# Top_board.net
KiCad netlist of a schematic drawn in Altium Designer
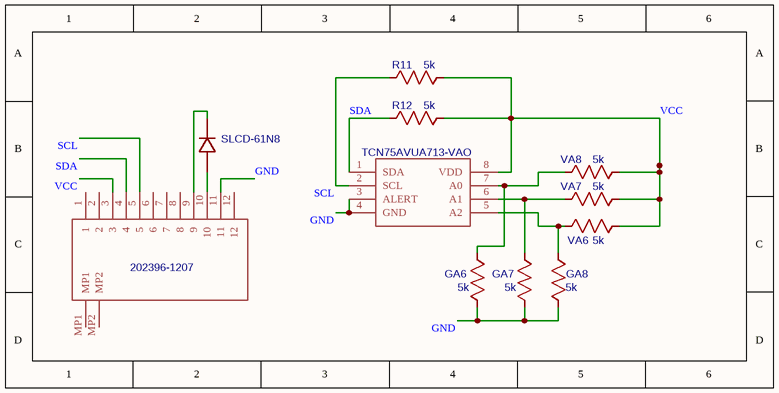
[diagram p0: Top_board.schdoc]

(export (version "E")
  (design (tool "Eeschema 10.0.6"))
  (components
    (comp (ref "D8")
      (value "SLCD-61N8")
      (footprint "SOD-123_L2.8-W1.8-LS3.7-RD")
      (fields
        (field (name "BOM_SUPPLIER PART") "C328592")
        (field (name "BOM_MANUFACTURER PART") "1N4007W")
        (field (name "CONTRIBUTOR") "Blothr")
      )
      (libsource (lib "altium-import") (part "root_1_SLCD-61N8_"))
    )
    (comp (ref "GA6")
      (value "5k")
      (footprint "R0805")
      (fields
        (field (name "BOM_SUPPLIER PART") "71-CRCW0805J-5K")
        (field (name "BOM_MANUFACTURER PART") "CRCW08055K00JNTA")
        (field (name "CONTRIBUTOR") "LCEDA_Lib")
      )
      (libsource (lib "altium-import") (part "root_1_5k_"))
    )
    (comp (ref "GA7")
      (value "5k")
      (footprint "R0805")
      (fields
        (field (name "BOM_SUPPLIER PART") "71-CRCW0805J-5K")
        (field (name "BOM_MANUFACTURER PART") "CRCW08055K00JNTA")
        (field (name "CONTRIBUTOR") "LCEDA_Lib")
      )
      (libsource (lib "altium-import") (part "root_1_5k_"))
    )
    (comp (ref "GA8")
      (value "5k")
      (footprint "R0805")
      (fields
        (field (name "BOM_SUPPLIER PART") "71-CRCW0805J-5K")
        (field (name "BOM_MANUFACTURER PART") "CRCW08055K00JNTA")
        (field (name "CONTRIBUTOR") "LCEDA_Lib")
      )
      (libsource (lib "altium-import") (part "root_1_5k_"))
    )
    (comp (ref "IC3")
      (value "TCN75AVUA713-VAO")
      (footprint "SOP65P490X110-8N")
      (libsource (lib "altium-import") (part "root_0_TCN75AVUA713-VAO_"))
    )
    (comp (ref "J2")
      (value "202396-1207")
      (footprint "2023961207")
      (fields (field (name "CONTRIBUTOR") "tomact"))
      (libsource (lib "altium-import") (part "root_1_202396-1207_"))
    )
    (comp (ref "R11")
      (value "5k")
      (footprint "R0805")
      (fields
        (field (name "BOM_SUPPLIER PART") "71-CRCW0805J-5K")
        (field (name "BOM_MANUFACTURER PART") "CRCW08055K00JNTA")
        (field (name "CONTRIBUTOR") "LCEDA_Lib")
      )
      (libsource (lib "altium-import") (part "root_0_5k_"))
    )
    (comp (ref "R12")
      (value "5k")
      (footprint "R0805")
      (fields
        (field (name "BOM_SUPPLIER PART") "71-CRCW0805J-5K")
        (field (name "BOM_MANUFACTURER PART") "CRCW08055K00JNTA")
        (field (name "CONTRIBUTOR") "LCEDA_Lib")
      )
      (libsource (lib "altium-import") (part "root_0_5k_"))
    )
    (comp (ref "VA6")
      (value "5k")
      (footprint "R0805")
      (fields
        (field (name "BOM_SUPPLIER PART") "71-CRCW0805J-5K")
        (field (name "BOM_MANUFACTURER PART") "CRCW08055K00JNTA")
        (field (name "CONTRIBUTOR") "LCEDA_Lib")
      )
      (libsource (lib "altium-import") (part "root_0_5k_"))
    )
    (comp (ref "VA7")
      (value "5k")
      (footprint "R0805")
      (fields
        (field (name "BOM_SUPPLIER PART") "71-CRCW0805J-5K")
        (field (name "BOM_MANUFACTURER PART") "CRCW08055K00JNTA")
        (field (name "CONTRIBUTOR") "LCEDA_Lib")
      )
      (libsource (lib "altium-import") (part "root_0_5k_"))
    )
    (comp (ref "VA8")
      (value "5k")
      (footprint "R0805")
      (fields
        (field (name "BOM_SUPPLIER PART") "71-CRCW0805J-5K")
        (field (name "BOM_MANUFACTURER PART") "CRCW08055K00JNTA")
        (field (name "CONTRIBUTOR") "LCEDA_Lib")
      )
      (libsource (lib "altium-import") (part "root_0_5k_"))
    )
  )
  (nets
    (net (code "1") (name "/GND") (class "Default")
      (node (ref "GA6") (pin "1") (pinfunction "1_1") (pintype "passive"))
      (node (ref "GA7") (pin "1") (pinfunction "1_1") (pintype "passive"))
      (node (ref "GA8") (pin "1") (pinfunction "1_1") (pintype "passive"))
      (node (ref "IC3") (pin "3") (pinfunction "ALERT_3") (pintype "passive"))
      (node (ref "IC3") (pin "4") (pinfunction "GND_4") (pintype "passive"))
      (node (ref "J2") (pin "11") (pinfunction "11_11") (pintype "passive"))
    )
    (net (code "2") (name "/SCL") (class "Default")
      (node (ref "IC3") (pin "2") (pinfunction "SCL_2") (pintype "passive"))
      (node (ref "J2") (pin "5") (pinfunction "5_5") (pintype "passive"))
      (node (ref "R11") (pin "1") (pinfunction "1_1") (pintype "passive"))
    )
    (net (code "3") (name "/SDA") (class "Default")
      (node (ref "IC3") (pin "1") (pinfunction "SDA_1") (pintype "passive"))
      (node (ref "J2") (pin "4") (pinfunction "4_4") (pintype "passive"))
      (node (ref "R12") (pin "1") (pinfunction "1_1") (pintype "passive"))
    )
    (net (code "4") (name "/VCC") (class "Default")
      (node (ref "IC3") (pin "8") (pinfunction "VDD_8") (pintype "passive"))
      (node (ref "J2") (pin "3") (pinfunction "3_3") (pintype "passive"))
      (node (ref "R11") (pin "2") (pinfunction "2_2") (pintype "passive"))
      (node (ref "R12") (pin "2") (pinfunction "2_2") (pintype "passive"))
      (node (ref "VA6") (pin "2") (pinfunction "2_2") (pintype "passive"))
      (node (ref "VA7") (pin "2") (pinfunction "2_2") (pintype "passive"))
      (node (ref "VA8") (pin "2") (pinfunction "2_2") (pintype "passive"))
    )
    (net (code "5") (name "Net-(D8-Pad1)") (class "Default")
      (node (ref "D8") (pin "1") (pinfunction "1_1") (pintype "passive"))
      (node (ref "J2") (pin "9") (pinfunction "9_9") (pintype "passive"))
    )
    (net (code "6") (name "Net-(D8-Pad2)") (class "Default")
      (node (ref "D8") (pin "2") (pinfunction "2_2") (pintype "passive"))
      (node (ref "J2") (pin "10") (pinfunction "10_10") (pintype "passive"))
    )
    (net (code "7") (name "Net-(IC3-A0)") (class "Default")
      (node (ref "GA6") (pin "2") (pinfunction "2_2") (pintype "passive"))
      (node (ref "IC3") (pin "7") (pinfunction "A0_7") (pintype "passive"))
      (node (ref "VA8") (pin "1") (pinfunction "1_1") (pintype "passive"))
    )
    (net (code "8") (name "Net-(IC3-A1)") (class "Default")
      (node (ref "GA7") (pin "2") (pinfunction "2_2") (pintype "passive"))
      (node (ref "IC3") (pin "6") (pinfunction "A1_6") (pintype "passive"))
      (node (ref "VA7") (pin "1") (pinfunction "1_1") (pintype "passive"))
    )
    (net (code "9") (name "Net-(IC3-A2)") (class "Default")
      (node (ref "GA8") (pin "2") (pinfunction "2_2") (pintype "passive"))
      (node (ref "IC3") (pin "5") (pinfunction "A2_5") (pintype "passive"))
      (node (ref "VA6") (pin "1") (pinfunction "1_1") (pintype "passive"))
    )
    (net (code "10") (name "unconnected-(J2-Pad1)") (class "Default")
      (node (ref "J2") (pin "1") (pinfunction "1_1") (pintype "passive"))
    )
    (net (code "11") (name "unconnected-(J2-Pad2)") (class "Default")
      (node (ref "J2") (pin "2") (pinfunction "2_2") (pintype "passive"))
    )
    (net (code "12") (name "unconnected-(J2-Pad6)") (class "Default")
      (node (ref "J2") (pin "6") (pinfunction "6_6") (pintype "passive"))
    )
    (net (code "13") (name "unconnected-(J2-Pad7)") (class "Default")
      (node (ref "J2") (pin "7") (pinfunction "7_7") (pintype "passive"))
    )
    (net (code "14") (name "unconnected-(J2-Pad8)") (class "Default")
      (node (ref "J2") (pin "8") (pinfunction "8_8") (pintype "passive"))
    )
    (net (code "15") (name "unconnected-(J2-Pad12)") (class "Default")
      (node (ref "J2") (pin "12") (pinfunction "12_12") (pintype "passive"))
    )
    (net (code "16") (name "unconnected-(J2-PadMP1)") (class "Default")
      (node (ref "J2") (pin "MP1") (pinfunction "MP1_MP1") (pintype "passive"))
    )
    (net (code "17") (name "unconnected-(J2-PadMP2)") (class "Default")
      (node (ref "J2") (pin "MP2") (pinfunction "MP2_MP2") (pintype "passive"))
    )
  )
)
